# 20180616.net
KiCad netlist of a schematic drawn in Altium Designer
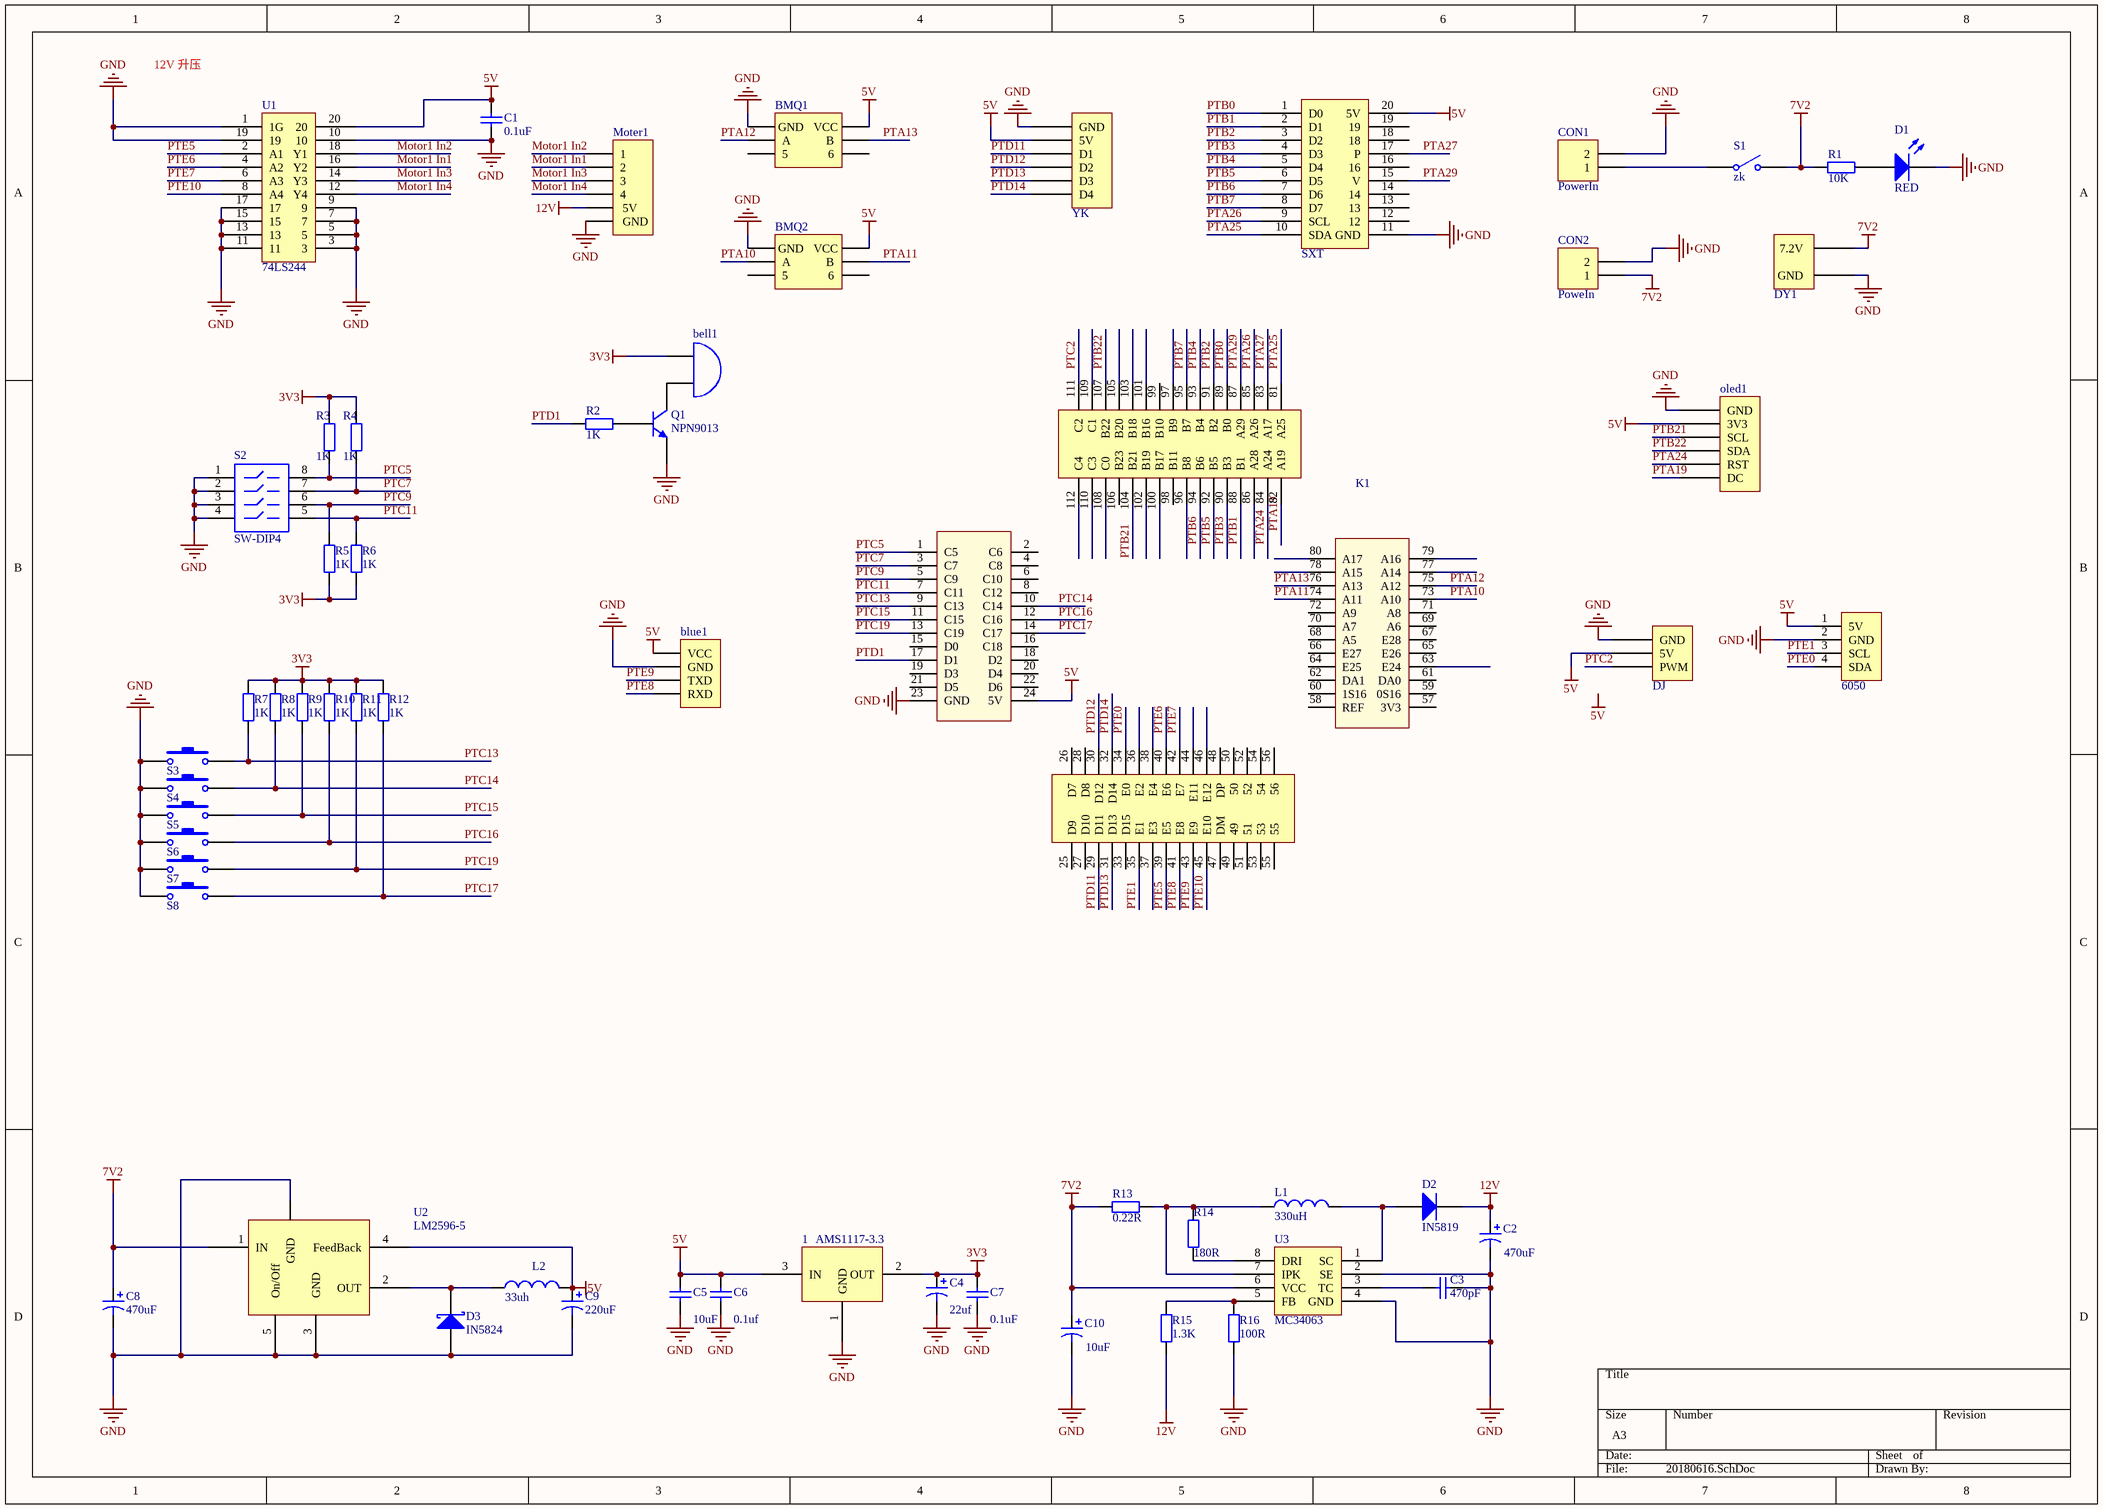
[diagram p0: 20180616.SchDoc]

(export (version "E")
  (design (tool "Eeschema 10.0.6"))
  (components
    (comp (ref "*") (value "6050") (footprint "HDR1X4") (libsource (lib "DS_zk") (part "6050")))
    (comp (ref "*1") (value "SXT") (footprint "SXT") (libsource (lib "DS_zk") (part "摄像头")))
    (comp (ref "*2") (value "YK") (footprint "HDR1X6") (libsource (lib "DS_zk") (part "遥控")))
    (comp (ref "*7") (value "DJ") (footprint "HDR1X3") (libsource (lib "DS_zk") (part "舵机")))
    (comp (ref "1")
      (value "AMS1117-3.3")
      (footprint "lm1117-5v")
      (libsource (lib "红牛板Schlib") (part "LT1117-3.3"))
    )
    (comp (ref "bell1")
      (value "Bell")
      (footprint "bezzer")
      (description "Electrical Bell")
      (fields (field (name "PUBLISHER") "Altium Limited"))
      (libsource (lib "Miscellaneous Devices") (part "Bell"))
    )
    (comp (ref "blue1") (value "blueteeth2") (footprint "HDR1X4") (libsource (lib "LY") (part "blueteeth")))
    (comp (ref "BMQ1") (value "encode_1") (footprint "HDR2X3") (libsource (lib "主控板原理图") (part "encode")))
    (comp (ref "BMQ2") (value "encode_2") (footprint "HDR2X3") (libsource (lib "主控板原理图") (part "encode")))
    (comp (ref "C1")
      (value "0.1uF")
      (footprint "0603")
      (description "Capacitor (Semiconductor SIM Model)")
      (fields (field (name "PUBLISHER") "Altium Limited"))
      (libsource (lib "Miscellaneous Devices") (part "Cap Semi"))
    )
    (comp (ref "C2")
      (value "470uF")
      (footprint "470UF")
      (description "Polarized Capacitor (Surface Mount)")
      (fields (field (name "PUBLISHER") "Altium Limited"))
      (libsource (lib "Miscellaneous Devices") (part "Cap Pol3"))
    )
    (comp (ref "C3")
      (value "470pF")
      (footprint "0805")
      (description "Capacitor (Semiconductor SIM Model)")
      (fields (field (name "PUBLISHER") "Altium Limited"))
      (libsource (lib "Miscellaneous Devices") (part "Cap Semi"))
    )
    (comp (ref "C4")
      (value "22uf")
      (footprint "0805")
      (description "Polarized Capacitor (Radial)")
      (fields (field (name "Comment") "Cap Pol1") (field (name "PUBLISHER") "Altium Limited"))
      (libsource (lib "Miscellaneous Devices") (part "Cap Pol1"))
    )
    (comp (ref "C5")
      (value "10uF")
      (footprint "0805")
      (description "Capacitor")
      (fields (field (name "Comment") "Cap") (field (name "PUBLISHER") "Altium Limited"))
      (libsource (lib "Miscellaneous Devices") (part "Cap"))
    )
    (comp (ref "C6")
      (value "0.1uf")
      (footprint "0805")
      (description "Capacitor")
      (fields (field (name "Comment") "Cap") (field (name "PUBLISHER") "Altium Limited"))
      (libsource (lib "Miscellaneous Devices") (part "Cap"))
    )
    (comp (ref "C7")
      (value "0.1uF")
      (footprint "0805")
      (description "Capacitor")
      (fields (field (name "Comment") "Cap") (field (name "PUBLISHER") "Altium Limited"))
      (libsource (lib "Miscellaneous Devices") (part "Cap"))
    )
    (comp (ref "C8")
      (value "470uF")
      (footprint "470uF")
      (description "Polarized Capacitor (Radial)")
      (fields (field (name "Comment") "Cap Pol1") (field (name "PUBLISHER") "Altium Limited"))
      (libsource (lib "主控板原理图") (part "Cap Pol1"))
    )
    (comp (ref "C9")
      (value "220uF")
      (footprint "220uf")
      (description "Polarized Capacitor (Radial)")
      (fields (field (name "Comment") "Cap Pol1") (field (name "PUBLISHER") "Altium Limited"))
      (libsource (lib "主控板原理图") (part "Cap Pol1"))
    )
    (comp (ref "C10")
      (value "10uF")
      (footprint "0805")
      (description "Polarized Capacitor (Surface Mount)")
      (fields (field (name "PUBLISHER") "Altium Limited"))
      (libsource (lib "Miscellaneous Devices") (part "Cap Pol3"))
    )
    (comp (ref "CON1")
      (value "PowerIn")
      (footprint "DIZUO")
      (description "Header, 2-Pin")
      (fields (field (name "PUBLISHER") "Altium Limited"))
      (libsource (lib "Miscellaneous Connectors") (part "Header 2"))
    )
    (comp (ref "CON2")
      (value "PoweIn")
      (footprint "KF301-2P")
      (description "Header, 2-Pin")
      (fields (field (name "PUBLISHER") "Altium Limited"))
      (libsource (lib "Miscellaneous Connectors") (part "Header 2"))
    )
    (comp (ref "D1")
      (value "RED")
      (footprint "0805LED")
      (description "Typical RED, GREEN, YELLOW, AMBER GaAs LED")
      (fields (field (name "PUBLISHER") "Altium Limited"))
      (libsource (lib "主控板原理图") (part "LED2"))
    )
    (comp (ref "D2")
      (value "IN5819")
      (footprint "1206(3216)")
      (description "Default Diode")
      (fields (field (name "PUBLISHER") "Altium Limited"))
      (libsource (lib "Miscellaneous Devices") (part "Diode"))
    )
    (comp (ref "D3") (value "IN5824") (footprint "1N5824") (libsource (lib "主控板原理图") (part "IN5824")))
    (comp (ref "DY1") (value "H1") (footprint "HDR1X2") (libsource (lib "DS_zk") (part "H1")))
    (comp (ref "K1") (value "K60") (footprint "K60") (libsource (lib "主控板原理图") (part "K60")))
    (comp (ref "L1")
      (value "330uH")
      (footprint "diangan")
      (description "Inductor")
      (fields (field (name "PUBLISHER") "Altium Limited"))
      (libsource (lib "Miscellaneous Devices") (part "Inductor"))
    )
    (comp (ref "L2")
      (value "33uh")
      (footprint "diangan")
      (description "Inductor")
      (fields (field (name "PUBLISHER") "Altium Limited"))
      (libsource (lib "主控板原理图") (part "Inductor"))
    )
    (comp (ref "Moter1") (value "Motor") (footprint "HDR1X6") (libsource (lib "主控板原理图") (part "Motor")))
    (comp (ref "oled1") (value "OLED") (footprint "HDR1X6") (libsource (lib "LY") (part "OLED")))
    (comp (ref "Q1")
      (value "NPN9013")
      (footprint "npn9013")
      (description "NPN General Purpose Amplifier")
      (fields (field (name "PUBLISHER") "Altium Limited"))
      (libsource (lib "Miscellaneous Devices") (part "2N3904"))
    )
    (comp (ref "R1")
      (value "10K")
      (footprint "0805")
      (description "Resistor")
      (fields (field (name "Comment") "Res2") (field (name "PUBLISHER") "Altium Limited"))
      (libsource (lib "") (part "Res2_2"))
    )
    (comp (ref "R2")
      (value "1K")
      (footprint "0805")
      (description "Resistor")
      (fields (field (name "Comment") "Res2") (field (name "PUBLISHER") "Altium Limited"))
      (libsource (lib "") (part "Res2_1"))
    )
    (comp (ref "R3")
      (value "1K")
      (footprint "0805")
      (description "Resistor")
      (fields (field (name "Comment") "Res2") (field (name "PUBLISHER") "Altium Limited"))
      (libsource (lib "") (part "Res2_3"))
    )
    (comp (ref "R4")
      (value "1K")
      (footprint "0805")
      (description "Resistor")
      (fields (field (name "Comment") "Res2") (field (name "PUBLISHER") "Altium Limited"))
      (libsource (lib "") (part "Res2_3"))
    )
    (comp (ref "R5")
      (value "1K")
      (footprint "0805")
      (description "Resistor")
      (fields (field (name "Comment") "Res2") (field (name "PUBLISHER") "Altium Limited"))
      (libsource (lib "主控板原理图") (part "Res2"))
    )
    (comp (ref "R6")
      (value "1K")
      (footprint "0805")
      (description "Resistor")
      (fields (field (name "Comment") "Res2") (field (name "PUBLISHER") "Altium Limited"))
      (libsource (lib "") (part "Res2_3"))
    )
    (comp (ref "R7")
      (value "1K")
      (footprint "0805")
      (description "Resistor")
      (fields (field (name "Comment") "Res2") (field (name "PUBLISHER") "Altium Limited"))
      (libsource (lib "") (part "Res2_3"))
    )
    (comp (ref "R8")
      (value "1K")
      (footprint "0805")
      (description "Resistor")
      (fields (field (name "Comment") "Res2") (field (name "PUBLISHER") "Altium Limited"))
      (libsource (lib "") (part "Res2_3"))
    )
    (comp (ref "R9")
      (value "1K")
      (footprint "0805")
      (description "Resistor")
      (fields (field (name "Comment") "Res2") (field (name "PUBLISHER") "Altium Limited"))
      (libsource (lib "") (part "Res2_3"))
    )
    (comp (ref "R10")
      (value "1K")
      (footprint "0805")
      (description "Resistor")
      (fields (field (name "Comment") "Res2") (field (name "PUBLISHER") "Altium Limited"))
      (libsource (lib "") (part "Res2_3"))
    )
    (comp (ref "R11")
      (value "1K")
      (footprint "0805")
      (description "Resistor")
      (fields (field (name "Comment") "Res2") (field (name "PUBLISHER") "Altium Limited"))
      (libsource (lib "") (part "Res2_3"))
    )
    (comp (ref "R12")
      (value "1K")
      (footprint "0805")
      (description "Resistor")
      (fields (field (name "Comment") "Res2") (field (name "PUBLISHER") "Altium Limited"))
      (libsource (lib "") (part "Res2_3"))
    )
    (comp (ref "R13")
      (value "0.22R")
      (footprint "0805")
      (description "Resistor")
      (fields (field (name "PUBLISHER") "Altium Limited"))
      (libsource (lib "") (part "Res2_2"))
    )
    (comp (ref "R14")
      (value "180R")
      (footprint "0805")
      (description "Resistor")
      (fields (field (name "PUBLISHER") "Altium Limited"))
      (libsource (lib "") (part "Res2_1"))
    )
    (comp (ref "R15")
      (value "1.3K")
      (footprint "0805")
      (description "Resistor")
      (fields (field (name "PUBLISHER") "Altium Limited"))
      (libsource (lib "Miscellaneous Devices") (part "Res2"))
    )
    (comp (ref "R16")
      (value "100R")
      (footprint "0805")
      (description "Resistor")
      (fields (field (name "PUBLISHER") "Altium Limited"))
      (libsource (lib "Miscellaneous Devices") (part "Res2"))
    )
    (comp (ref "S1")
      (value "zk")
      (footprint "SWITCH-MID")
      (description "Single-Pole, Single-Throw Switch")
      (fields (field (name "PUBLISHER") "Altium Limited"))
      (libsource (lib "Miscellaneous Devices") (part "SW-SPST"))
    )
    (comp (ref "S2")
      (value "SW-DIP4")
      (footprint "BMKG")
      (description "DIP Switch")
      (fields (field (name "PUBLISHER") "Altium Limited"))
      (libsource (lib "主控板原理图") (part "SW-DIP4"))
    )
    (comp (ref "S3")
      (value "SW-PB")
      (footprint "BUTTON")
      (description "Switch")
      (fields (field (name "PUBLISHER") "Altium Limited"))
      (libsource (lib "主控板原理图") (part "SW-PB"))
    )
    (comp (ref "S4")
      (value "SW-PB")
      (footprint "BUTTON")
      (description "Switch")
      (fields (field (name "PUBLISHER") "Altium Limited"))
      (libsource (lib "主控板原理图") (part "SW-PB"))
    )
    (comp (ref "S5")
      (value "SW-PB")
      (footprint "BUTTON")
      (description "Switch")
      (fields (field (name "PUBLISHER") "Altium Limited"))
      (libsource (lib "主控板原理图") (part "SW-PB"))
    )
    (comp (ref "S6")
      (value "SW-PB")
      (footprint "BUTTON")
      (description "Switch")
      (fields (field (name "PUBLISHER") "Altium Limited"))
      (libsource (lib "主控板原理图") (part "SW-PB"))
    )
    (comp (ref "S7")
      (value "SW-PB")
      (footprint "BUTTON")
      (description "Switch")
      (fields (field (name "PUBLISHER") "Altium Limited"))
      (libsource (lib "主控板原理图") (part "SW-PB"))
    )
    (comp (ref "S8")
      (value "SW-PB")
      (footprint "BUTTON")
      (description "Switch")
      (fields (field (name "PUBLISHER") "Altium Limited"))
      (libsource (lib "主控板原理图") (part "SW-PB"))
    )
    (comp (ref "U1") (value "74LS244") (footprint "74ls244DB") (libsource (lib "ly") (part "74LS244")))
    (comp (ref "U2") (value "LM2596-5") (footprint "LM2596") (libsource (lib "主控板原理图") (part "LM2596")))
    (comp (ref "U3") (value "MC34063") (footprint "MC34063") (libsource (lib "LY") (part "MC34063")))
  )
  (nets
    (net (code "1") (name "/Motor1 In1") (class "Default")
      (node (ref "Moter1") (pin "2") (pinfunction "2_2") (pintype "passive"))
      (node (ref "U1") (pin "16") (pinfunction "Y2_16") (pintype "passive"))
    )
    (net (code "2") (name "/Motor1 In2") (class "Default")
      (node (ref "Moter1") (pin "1") (pinfunction "1_1") (pintype "passive"))
      (node (ref "U1") (pin "18") (pinfunction "Y1_18") (pintype "passive"))
    )
    (net (code "3") (name "/Motor1 In3") (class "Default")
      (node (ref "Moter1") (pin "3") (pinfunction "3_3") (pintype "passive"))
      (node (ref "U1") (pin "14") (pinfunction "Y3_14") (pintype "passive"))
    )
    (net (code "4") (name "/Motor1 In4") (class "Default")
      (node (ref "Moter1") (pin "4") (pinfunction "4_4") (pintype "passive"))
      (node (ref "U1") (pin "12") (pinfunction "Y4_12") (pintype "passive"))
    )
    (net (code "5") (name "/PTA10") (class "Default")
      (node (ref "BMQ2") (pin "3") (pinfunction "A_3") (pintype "passive"))
      (node (ref "K1") (pin "73") (pinfunction "A10_73") (pintype "passive"))
    )
    (net (code "6") (name "/PTA11") (class "Default")
      (node (ref "BMQ2") (pin "4") (pinfunction "B_4") (pintype "passive"))
      (node (ref "K1") (pin "74") (pinfunction "A11_74") (pintype "passive"))
    )
    (net (code "7") (name "/PTA12") (class "Default")
      (node (ref "BMQ1") (pin "3") (pinfunction "A_3") (pintype "passive"))
      (node (ref "K1") (pin "75") (pinfunction "A12_75") (pintype "passive"))
    )
    (net (code "8") (name "/PTA13") (class "Default")
      (node (ref "BMQ1") (pin "4") (pinfunction "B_4") (pintype "passive"))
      (node (ref "K1") (pin "76") (pinfunction "A13_76") (pintype "passive"))
    )
    (net (code "9") (name "/PTA19") (class "Default")
      (node (ref "K1") (pin "82") (pinfunction "A19_82") (pintype "passive"))
      (node (ref "oled1") (pin "6") (pinfunction "DC_6") (pintype "passive"))
    )
    (net (code "10") (name "/PTA24") (class "Default")
      (node (ref "K1") (pin "84") (pinfunction "A24_84") (pintype "passive"))
      (node (ref "oled1") (pin "5") (pinfunction "RST_5") (pintype "passive"))
    )
    (net (code "11") (name "/PTA25") (class "Default")
      (node (ref "*1") (pin "10") (pinfunction "SDA_10") (pintype "passive"))
      (node (ref "K1") (pin "81") (pinfunction "A25_81") (pintype "passive"))
    )
    (net (code "12") (name "/PTA26") (class "Default")
      (node (ref "*1") (pin "9") (pinfunction "SCL_9") (pintype "passive"))
      (node (ref "K1") (pin "85") (pinfunction "A26_85") (pintype "passive"))
    )
    (net (code "13") (name "/PTA27") (class "Default")
      (node (ref "*1") (pin "17") (pinfunction "P_17") (pintype "passive"))
      (node (ref "K1") (pin "83") (pinfunction "A17_83") (pintype "passive"))
    )
    (net (code "14") (name "/PTA29") (class "Default")
      (node (ref "*1") (pin "15") (pinfunction "V_15") (pintype "passive"))
      (node (ref "K1") (pin "87") (pinfunction "A29_87") (pintype "passive"))
    )
    (net (code "15") (name "/PTB0") (class "Default")
      (node (ref "*1") (pin "1") (pinfunction "D0_1") (pintype "passive"))
      (node (ref "K1") (pin "89") (pinfunction "B0_89") (pintype "passive"))
    )
    (net (code "16") (name "/PTB1") (class "Default")
      (node (ref "*1") (pin "2") (pinfunction "D1_2") (pintype "passive"))
      (node (ref "K1") (pin "88") (pinfunction "B1_88") (pintype "passive"))
    )
    (net (code "17") (name "/PTB2") (class "Default")
      (node (ref "*1") (pin "3") (pinfunction "D2_3") (pintype "passive"))
      (node (ref "K1") (pin "91") (pinfunction "B2_91") (pintype "passive"))
    )
    (net (code "18") (name "/PTB3") (class "Default")
      (node (ref "*1") (pin "4") (pinfunction "D3_4") (pintype "passive"))
      (node (ref "K1") (pin "90") (pinfunction "B3_90") (pintype "passive"))
    )
    (net (code "19") (name "/PTB4") (class "Default")
      (node (ref "*1") (pin "5") (pinfunction "D4_5") (pintype "passive"))
      (node (ref "K1") (pin "93") (pinfunction "B4_93") (pintype "passive"))
    )
    (net (code "20") (name "/PTB5") (class "Default")
      (node (ref "*1") (pin "6") (pinfunction "D5_6") (pintype "passive"))
      (node (ref "K1") (pin "92") (pinfunction "B5_92") (pintype "passive"))
    )
    (net (code "21") (name "/PTB6") (class "Default")
      (node (ref "*1") (pin "7") (pinfunction "D6_7") (pintype "passive"))
      (node (ref "K1") (pin "94") (pinfunction "B6_94") (pintype "passive"))
    )
    (net (code "22") (name "/PTB7") (class "Default")
      (node (ref "*1") (pin "8") (pinfunction "D7_8") (pintype "passive"))
      (node (ref "K1") (pin "95") (pinfunction "B7_95") (pintype "passive"))
    )
    (net (code "23") (name "/PTB21") (class "Default")
      (node (ref "K1") (pin "104") (pinfunction "B21_104") (pintype "passive"))
      (node (ref "oled1") (pin "3") (pinfunction "SCL_3") (pintype "passive"))
    )
    (net (code "24") (name "/PTB22") (class "Default")
      (node (ref "K1") (pin "107") (pinfunction "B22_107") (pintype "passive"))
      (node (ref "oled1") (pin "4") (pinfunction "SDA_4") (pintype "passive"))
    )
    (net (code "25") (name "/PTC2") (class "Default")
      (node (ref "*7") (pin "3") (pinfunction "PWM_3") (pintype "passive"))
      (node (ref "K1") (pin "111") (pinfunction "C2_111") (pintype "passive"))
    )
    (net (code "26") (name "/PTC5") (class "Default")
      (node (ref "K1") (pin "1") (pinfunction "C5_1") (pintype "passive"))
      (node (ref "R3") (pin "1") (pinfunction "1_1") (pintype "passive"))
      (node (ref "S2") (pin "8") (pinfunction "8_8") (pintype "passive"))
    )
    (net (code "27") (name "/PTC7") (class "Default")
      (node (ref "K1") (pin "3") (pinfunction "C7_3") (pintype "passive"))
      (node (ref "R4") (pin "1") (pinfunction "1_1") (pintype "passive"))
      (node (ref "S2") (pin "7") (pinfunction "7_7") (pintype "passive"))
    )
    (net (code "28") (name "/PTC9") (class "Default")
      (node (ref "K1") (pin "5") (pinfunction "C9_5") (pintype "passive"))
      (node (ref "R5") (pin "1") (pinfunction "1_1") (pintype "passive"))
      (node (ref "S2") (pin "6") (pinfunction "6_6") (pintype "passive"))
    )
    (net (code "29") (name "/PTC11") (class "Default")
      (node (ref "K1") (pin "7") (pinfunction "C11_7") (pintype "passive"))
      (node (ref "R6") (pin "2") (pinfunction "2_2") (pintype "passive"))
      (node (ref "S2") (pin "5") (pinfunction "5_5") (pintype "passive"))
    )
    (net (code "30") (name "/PTC13") (class "Default")
      (node (ref "K1") (pin "9") (pinfunction "C13_9") (pintype "passive"))
      (node (ref "R7") (pin "1") (pinfunction "1_1") (pintype "passive"))
      (node (ref "S3") (pin "2") (pinfunction "2_2") (pintype "passive"))
    )
    (net (code "31") (name "/PTC14") (class "Default")
      (node (ref "K1") (pin "10") (pinfunction "C14_10") (pintype "passive"))
      (node (ref "R8") (pin "1") (pinfunction "1_1") (pintype "passive"))
      (node (ref "S4") (pin "2") (pinfunction "2_2") (pintype "passive"))
    )
    (net (code "32") (name "/PTC15") (class "Default")
      (node (ref "K1") (pin "11") (pinfunction "C15_11") (pintype "passive"))
      (node (ref "R9") (pin "1") (pinfunction "1_1") (pintype "passive"))
      (node (ref "S5") (pin "2") (pinfunction "2_2") (pintype "passive"))
    )
    (net (code "33") (name "/PTC16") (class "Default")
      (node (ref "K1") (pin "12") (pinfunction "C16_12") (pintype "passive"))
      (node (ref "R10") (pin "1") (pinfunction "1_1") (pintype "passive"))
      (node (ref "S6") (pin "2") (pinfunction "2_2") (pintype "passive"))
    )
    (net (code "34") (name "/PTC17") (class "Default")
      (node (ref "K1") (pin "14") (pinfunction "C17_14") (pintype "passive"))
      (node (ref "R12") (pin "1") (pinfunction "1_1") (pintype "passive"))
      (node (ref "S8") (pin "2") (pinfunction "2_2") (pintype "passive"))
    )
    (net (code "35") (name "/PTC19") (class "Default")
      (node (ref "K1") (pin "13") (pinfunction "C19_13") (pintype "passive"))
      (node (ref "R11") (pin "1") (pinfunction "1_1") (pintype "passive"))
      (node (ref "S7") (pin "2") (pinfunction "2_2") (pintype "passive"))
    )
    (net (code "36") (name "/PTD1") (class "Default")
      (node (ref "K1") (pin "17") (pinfunction "D1_17") (pintype "passive"))
      (node (ref "R2") (pin "1") (pinfunction "1_1") (pintype "passive"))
    )
    (net (code "37") (name "/PTD11") (class "Default")
      (node (ref "*2") (pin "3") (pinfunction "D1_3") (pintype "passive"))
      (node (ref "K1") (pin "29") (pinfunction "D11_29") (pintype "passive"))
    )
    (net (code "38") (name "/PTD12") (class "Default")
      (node (ref "*2") (pin "4") (pinfunction "D2_4") (pintype "passive"))
      (node (ref "K1") (pin "30") (pinfunction "D12_30") (pintype "passive"))
    )
    (net (code "39") (name "/PTD13") (class "Default")
      (node (ref "*2") (pin "5") (pinfunction "D3_5") (pintype "passive"))
      (node (ref "K1") (pin "31") (pinfunction "D13_31") (pintype "passive"))
    )
    (net (code "40") (name "/PTD14") (class "Default")
      (node (ref "*2") (pin "6") (pinfunction "D4_6") (pintype "passive"))
      (node (ref "K1") (pin "32") (pinfunction "D14_32") (pintype "passive"))
    )
    (net (code "41") (name "/PTE0") (class "Default")
      (node (ref "*") (pin "4") (pinfunction "SDA_4") (pintype "passive"))
      (node (ref "K1") (pin "34") (pinfunction "E0_34") (pintype "passive"))
    )
    (net (code "42") (name "/PTE1") (class "Default")
      (node (ref "*") (pin "3") (pinfunction "SCL_3") (pintype "passive"))
      (node (ref "K1") (pin "35") (pinfunction "E1_35") (pintype "passive"))
    )
    (net (code "43") (name "/PTE5") (class "Default")
      (node (ref "K1") (pin "39") (pinfunction "E5_39") (pintype "passive"))
      (node (ref "U1") (pin "2") (pinfunction "A1_2") (pintype "passive"))
    )
    (net (code "44") (name "/PTE6") (class "Default")
      (node (ref "K1") (pin "40") (pinfunction "E6_40") (pintype "passive"))
      (node (ref "U1") (pin "4") (pinfunction "A2_4") (pintype "passive"))
    )
    (net (code "45") (name "/PTE7") (class "Default")
      (node (ref "K1") (pin "42") (pinfunction "E7_42") (pintype "passive"))
      (node (ref "U1") (pin "6") (pinfunction "A3_6") (pintype "passive"))
    )
    (net (code "46") (name "/PTE8") (class "Default")
      (node (ref "K1") (pin "41") (pinfunction "E8_41") (pintype "passive"))
      (node (ref "blue1") (pin "4") (pinfunction "RXD_4") (pintype "passive"))
    )
    (net (code "47") (name "/PTE9") (class "Default")
      (node (ref "K1") (pin "43") (pinfunction "E9_43") (pintype "passive"))
      (node (ref "blue1") (pin "3") (pinfunction "TXD_3") (pintype "passive"))
    )
    (net (code "48") (name "/PTE10") (class "Default")
      (node (ref "K1") (pin "45") (pinfunction "E10_45") (pintype "passive"))
      (node (ref "U1") (pin "8") (pinfunction "A4_8") (pintype "passive"))
    )
    (net (code "49") (name "3V3") (class "Default")
      (node (ref "1") (pin "2") (pinfunction "OUT_2") (pintype "open_emitter"))
      (node (ref "C4") (pin "1") (pinfunction "1_1") (pintype "passive"))
      (node (ref "C7") (pin "2") (pinfunction "2_2") (pintype "passive"))
      (node (ref "R10") (pin "2") (pinfunction "2_2") (pintype "passive"))
      (node (ref "R11") (pin "2") (pinfunction "2_2") (pintype "passive"))
      (node (ref "R12") (pin "2") (pinfunction "2_2") (pintype "passive"))
      (node (ref "R3") (pin "2") (pinfunction "2_2") (pintype "passive"))
      (node (ref "R4") (pin "2") (pinfunction "2_2") (pintype "passive"))
      (node (ref "R5") (pin "2") (pinfunction "2_2") (pintype "passive"))
      (node (ref "R6") (pin "1") (pinfunction "1_1") (pintype "passive"))
      (node (ref "R7") (pin "2") (pinfunction "2_2") (pintype "passive"))
      (node (ref "R8") (pin "2") (pinfunction "2_2") (pintype "passive"))
      (node (ref "R9") (pin "2") (pinfunction "2_2") (pintype "passive"))
      (node (ref "bell1") (pin "1") (pinfunction "A_1") (pintype "passive"))
    )
    (net (code "50") (name "5V") (class "Default")
      (node (ref "*") (pin "1") (pinfunction "5V_1") (pintype "passive"))
      (node (ref "*1") (pin "20") (pinfunction "5V_20") (pintype "passive"))
      (node (ref "*2") (pin "2") (pinfunction "5V_2") (pintype "passive"))
      (node (ref "*7") (pin "2") (pinfunction "5V_2") (pintype "passive"))
      (node (ref "1") (pin "3") (pinfunction "IN_3") (pintype "open_emitter"))
      (node (ref "BMQ1") (pin "2") (pinfunction "VCC_2") (pintype "passive"))
      (node (ref "BMQ2") (pin "2") (pinfunction "VCC_2") (pintype "passive"))
      (node (ref "C1") (pin "2") (pinfunction "2_2") (pintype "passive"))
      (node (ref "C5") (pin "2") (pinfunction "2_2") (pintype "passive"))
      (node (ref "C6") (pin "2") (pinfunction "2_2") (pintype "passive"))
      (node (ref "C9") (pin "1") (pinfunction "1_1") (pintype "passive"))
      (node (ref "K1") (pin "24") (pinfunction "5V_24") (pintype "passive"))
      (node (ref "L2") (pin "2") (pinfunction "2_2") (pintype "passive"))
      (node (ref "U1") (pin "20") (pinfunction "20_20") (pintype "passive"))
      (node (ref "U2") (pin "4") (pinfunction "FeedBack_4") (pintype "passive"))
      (node (ref "blue1") (pin "1") (pinfunction "VCC_1") (pintype "passive"))
      (node (ref "oled1") (pin "2") (pinfunction "3V3_2") (pintype "passive"))
    )
    (net (code "51") (name "7V2") (class "Default")
      (node (ref "C10") (pin "1") (pinfunction "1_1") (pintype "passive"))
      (node (ref "C8") (pin "1") (pinfunction "1_1") (pintype "passive"))
      (node (ref "CON2") (pin "1") (pinfunction "1_1") (pintype "passive"))
      (node (ref "DY1") (pin "2") (pinfunction "7.2V_2") (pintype "passive"))
      (node (ref "R1") (pin "2") (pinfunction "2_2") (pintype "passive"))
      (node (ref "R13") (pin "2") (pinfunction "2_2") (pintype "passive"))
      (node (ref "S1") (pin "2") (pinfunction "NO_2") (pintype "passive"))
      (node (ref "U2") (pin "1") (pinfunction "IN_1") (pintype "passive"))
      (node (ref "U3") (pin "6") (pinfunction "VCC_6") (pintype "passive"))
    )
    (net (code "52") (name "12V") (class "Default")
      (node (ref "C2") (pin "1") (pinfunction "1_1") (pintype "passive"))
      (node (ref "D2") (pin "2") (pinfunction "K_2") (pintype "passive"))
      (node (ref "Moter1") (pin "5") (pinfunction "5V_5") (pintype "passive"))
      (node (ref "R15") (pin "2") (pinfunction "2_2") (pintype "passive"))
    )
    (net (code "53") (name "GND") (class "Default")
      (node (ref "*") (pin "2") (pinfunction "GND_2") (pintype "passive"))
      (node (ref "*1") (pin "11") (pinfunction "GND_11") (pintype "passive"))
      (node (ref "*2") (pin "1") (pinfunction "GND_1") (pintype "passive"))
      (node (ref "*7") (pin "1") (pinfunction "GND_1") (pintype "passive"))
      (node (ref "1") (pin "1") (pinfunction "GND_1") (pintype "open_emitter"))
      (node (ref "BMQ1") (pin "1") (pinfunction "GND_1") (pintype "passive"))
      (node (ref "BMQ2") (pin "1") (pinfunction "GND_1") (pintype "passive"))
      (node (ref "C1") (pin "1") (pinfunction "1_1") (pintype "passive"))
      (node (ref "C10") (pin "2") (pinfunction "2_2") (pintype "passive"))
      (node (ref "C2") (pin "2") (pinfunction "2_2") (pintype "passive"))
      (node (ref "C3") (pin "2") (pinfunction "2_2") (pintype "passive"))
      (node (ref "C4") (pin "2") (pinfunction "2_2") (pintype "passive"))
      (node (ref "C5") (pin "1") (pinfunction "1_1") (pintype "passive"))
      (node (ref "C6") (pin "1") (pinfunction "1_1") (pintype "passive"))
      (node (ref "C7") (pin "1") (pinfunction "1_1") (pintype "passive"))
      (node (ref "C8") (pin "2") (pinfunction "2_2") (pintype "passive"))
      (node (ref "C9") (pin "2") (pinfunction "2_2") (pintype "passive"))
      (node (ref "CON1") (pin "2") (pinfunction "2_2") (pintype "passive"))
      (node (ref "CON2") (pin "2") (pinfunction "2_2") (pintype "passive"))
      (node (ref "D1") (pin "2") (pinfunction "K_2") (pintype "passive"))
      (node (ref "D3") (pin "2") (pinfunction "K_2") (pintype "passive"))
      (node (ref "DY1") (pin "1") (pinfunction "GND_1") (pintype "passive"))
      (node (ref "K1") (pin "23") (pinfunction "GND_23") (pintype "passive"))
      (node (ref "Moter1") (pin "6") (pinfunction "GND_6") (pintype "passive"))
      (node (ref "Q1") (pin "1") (pinfunction "E_1") (pintype "passive"))
      (node (ref "R16") (pin "2") (pinfunction "2_2") (pintype "passive"))
      (node (ref "S2") (pin "1") (pinfunction "1_1") (pintype "passive"))
      (node (ref "S2") (pin "2") (pinfunction "2_2") (pintype "passive"))
      (node (ref "S2") (pin "3") (pinfunction "3_3") (pintype "passive"))
      (node (ref "S2") (pin "4") (pinfunction "4_4") (pintype "passive"))
      (node (ref "S3") (pin "1") (pinfunction "1_1") (pintype "passive"))
      (node (ref "S4") (pin "1") (pinfunction "1_1") (pintype "passive"))
      (node (ref "S5") (pin "1") (pinfunction "1_1") (pintype "passive"))
      (node (ref "S6") (pin "1") (pinfunction "1_1") (pintype "passive"))
      (node (ref "S7") (pin "1") (pinfunction "1_1") (pintype "passive"))
      (node (ref "S8") (pin "1") (pinfunction "1_1") (pintype "passive"))
      (node (ref "U1") (pin "1") (pinfunction "1G_1") (pintype "passive"))
      (node (ref "U1") (pin "10") (pinfunction "10_10") (pintype "passive"))
      (node (ref "U1") (pin "11") (pinfunction "11_11") (pintype "passive"))
      (node (ref "U1") (pin "13") (pinfunction "13_13") (pintype "passive"))
      (node (ref "U1") (pin "15") (pinfunction "15_15") (pintype "passive"))
      (node (ref "U1") (pin "17") (pinfunction "17_17") (pintype "passive"))
      (node (ref "U1") (pin "19") (pinfunction "19_19") (pintype "passive"))
      (node (ref "U1") (pin "3") (pinfunction "3_3") (pintype "passive"))
      (node (ref "U1") (pin "5") (pinfunction "5_5") (pintype "passive"))
      (node (ref "U1") (pin "7") (pinfunction "7_7") (pintype "passive"))
      (node (ref "U1") (pin "9") (pinfunction "9_9") (pintype "passive"))
      (node (ref "U2") (pin "3") (pinfunction "GND_3") (pintype "passive"))
      (node (ref "U2") (pin "5") (pinfunction "On/Off_5") (pintype "passive"))
      (node (ref "U2") (pin "6") (pinfunction "GND_6") (pintype "passive"))
      (node (ref "U3") (pin "2") (pinfunction "SE_2") (pintype "passive"))
      (node (ref "U3") (pin "4") (pinfunction "GND_4") (pintype "passive"))
      (node (ref "blue1") (pin "2") (pinfunction "GND_2") (pintype "passive"))
      (node (ref "oled1") (pin "1") (pinfunction "GND_1") (pintype "passive"))
    )
    (net (code "54") (name "Net-(D1-A)") (class "Default")
      (node (ref "D1") (pin "1") (pinfunction "A_1") (pintype "passive"))
      (node (ref "R1") (pin "1") (pinfunction "1_1") (pintype "passive"))
    )
    (net (code "55") (name "Net-(D2-A)") (class "Default")
      (node (ref "D2") (pin "1") (pinfunction "A_1") (pintype "passive"))
      (node (ref "L1") (pin "2") (pinfunction "2_2") (pintype "passive"))
      (node (ref "U3") (pin "1") (pinfunction "SC_1") (pintype "passive"))
    )
    (net (code "56") (name "Net-(D3-A)") (class "Default")
      (node (ref "D3") (pin "1") (pinfunction "A_1") (pintype "passive"))
      (node (ref "L2") (pin "1") (pinfunction "1_1") (pintype "passive"))
      (node (ref "U2") (pin "2") (pinfunction "OUT_2") (pintype "passive"))
    )
    (net (code "57") (name "Net-(Q1-B)") (class "Default")
      (node (ref "Q1") (pin "2") (pinfunction "B_2") (pintype "passive"))
      (node (ref "R2") (pin "2") (pinfunction "2_2") (pintype "passive"))
    )
    (net (code "58") (name "Net-(Q1-C)") (class "Default")
      (node (ref "Q1") (pin "3") (pinfunction "C_3") (pintype "passive"))
      (node (ref "bell1") (pin "2") (pinfunction "B_2") (pintype "passive"))
    )
    (net (code "59") (name "Net-(S1-COMMON)") (class "Default")
      (node (ref "CON1") (pin "1") (pinfunction "1_1") (pintype "passive"))
      (node (ref "S1") (pin "1") (pinfunction "COMMON_1") (pintype "passive"))
    )
    (net (code "60") (name "Net-(U3-DRI)") (class "Default")
      (node (ref "R14") (pin "1") (pinfunction "1_1") (pintype "passive"))
      (node (ref "U3") (pin "8") (pinfunction "DRI_8") (pintype "passive"))
    )
    (net (code "61") (name "Net-(U3-FB)") (class "Default")
      (node (ref "R15") (pin "1") (pinfunction "1_1") (pintype "passive"))
      (node (ref "R16") (pin "1") (pinfunction "1_1") (pintype "passive"))
      (node (ref "U3") (pin "5") (pinfunction "FB_5") (pintype "passive"))
    )
    (net (code "62") (name "Net-(U3-IPK)") (class "Default")
      (node (ref "L1") (pin "1") (pinfunction "1_1") (pintype "passive"))
      (node (ref "R13") (pin "1") (pinfunction "1_1") (pintype "passive"))
      (node (ref "R14") (pin "2") (pinfunction "2_2") (pintype "passive"))
      (node (ref "U3") (pin "7") (pinfunction "IPK_7") (pintype "passive"))
    )
    (net (code "63") (name "Net-(U3-TC)") (class "Default")
      (node (ref "C3") (pin "1") (pinfunction "1_1") (pintype "passive"))
      (node (ref "U3") (pin "3") (pinfunction "TC_3") (pintype "passive"))
    )
    (net (code "64") (name "unconnected-(*1-Pad12)") (class "Default")
      (node (ref "*1") (pin "12") (pinfunction "12_12") (pintype "passive"))
    )
    (net (code "65") (name "unconnected-(*1-Pad13)") (class "Default")
      (node (ref "*1") (pin "13") (pinfunction "13_13") (pintype "passive"))
    )
    (net (code "66") (name "unconnected-(*1-Pad14)") (class "Default")
      (node (ref "*1") (pin "14") (pinfunction "14_14") (pintype "passive"))
    )
    (net (code "67") (name "unconnected-(*1-Pad16)") (class "Default")
      (node (ref "*1") (pin "16") (pinfunction "16_16") (pintype "passive"))
    )
    (net (code "68") (name "unconnected-(*1-Pad18)") (class "Default")
      (node (ref "*1") (pin "18") (pinfunction "18_18") (pintype "passive"))
    )
    (net (code "69") (name "unconnected-(*1-Pad19)") (class "Default")
      (node (ref "*1") (pin "19") (pinfunction "19_19") (pintype "passive"))
    )
    (net (code "70") (name "unconnected-(BMQ1-Pad5)") (class "Default")
      (node (ref "BMQ1") (pin "5") (pinfunction "5_5") (pintype "passive"))
    )
    (net (code "71") (name "unconnected-(BMQ1-Pad6)") (class "Default")
      (node (ref "BMQ1") (pin "6") (pinfunction "6_6") (pintype "passive"))
    )
    (net (code "72") (name "unconnected-(BMQ2-Pad5)") (class "Default")
      (node (ref "BMQ2") (pin "5") (pinfunction "5_5") (pintype "passive"))
    )
    (net (code "73") (name "unconnected-(BMQ2-Pad6)") (class "Default")
      (node (ref "BMQ2") (pin "6") (pinfunction "6_6") (pintype "passive"))
    )
    (net (code "74") (name "unconnected-(K1-0S16-Pad59)") (class "Default")
      (node (ref "K1") (pin "59") (pinfunction "0S16_59") (pintype "passive"))
    )
    (net (code "75") (name "unconnected-(K1-1S16-Pad60)") (class "Default")
      (node (ref "K1") (pin "60") (pinfunction "1S16_60") (pintype "passive"))
    )
    (net (code "76") (name "unconnected-(K1-3V3-Pad57)") (class "Default")
      (node (ref "K1") (pin "57") (pinfunction "3V3_57") (pintype "passive"))
    )
    (net (code "77") (name "unconnected-(K1-A5-Pad68)") (class "Default")
      (node (ref "K1") (pin "68") (pinfunction "A5_68") (pintype "passive"))
    )
    (net (code "78") (name "unconnected-(K1-A6-Pad69)") (class "Default")
      (node (ref "K1") (pin "69") (pinfunction "A6_69") (pintype "passive"))
    )
    (net (code "79") (name "unconnected-(K1-A7-Pad70)") (class "Default")
      (node (ref "K1") (pin "70") (pinfunction "A7_70") (pintype "passive"))
    )
    (net (code "80") (name "unconnected-(K1-A8-Pad71)") (class "Default")
      (node (ref "K1") (pin "71") (pinfunction "A8_71") (pintype "passive"))
    )
    (net (code "81") (name "unconnected-(K1-A9-Pad72)") (class "Default")
      (node (ref "K1") (pin "72") (pinfunction "A9_72") (pintype "passive"))
    )
    (net (code "82") (name "unconnected-(K1-A14-Pad77)") (class "Default")
      (node (ref "K1") (pin "77") (pinfunction "A14_77") (pintype "passive"))
    )
    (net (code "83") (name "unconnected-(K1-A15-Pad78)") (class "Default")
      (node (ref "K1") (pin "78") (pinfunction "A15_78") (pintype "passive"))
    )
    (net (code "84") (name "unconnected-(K1-A16-Pad79)") (class "Default")
      (node (ref "K1") (pin "79") (pinfunction "A16_79") (pintype "passive"))
    )
    (net (code "85") (name "unconnected-(K1-A17-Pad80)") (class "Default")
      (node (ref "K1") (pin "80") (pinfunction "A17_80") (pintype "passive"))
    )
    (net (code "86") (name "unconnected-(K1-A28-Pad86)") (class "Default")
      (node (ref "K1") (pin "86") (pinfunction "A28_86") (pintype "passive"))
    )
    (net (code "87") (name "unconnected-(K1-B8-Pad96)") (class "Default")
      (node (ref "K1") (pin "96") (pinfunction "B8_96") (pintype "passive"))
    )
    (net (code "88") (name "unconnected-(K1-B9-Pad97)") (class "Default")
      (node (ref "K1") (pin "97") (pinfunction "B9_97") (pintype "passive"))
    )
    (net (code "89") (name "unconnected-(K1-B10-Pad99)") (class "Default")
      (node (ref "K1") (pin "99") (pinfunction "B10_99") (pintype "passive"))
    )
    (net (code "90") (name "unconnected-(K1-B11-Pad98)") (class "Default")
      (node (ref "K1") (pin "98") (pinfunction "B11_98") (pintype "passive"))
    )
    (net (code "91") (name "unconnected-(K1-B16-Pad101)") (class "Default")
      (node (ref "K1") (pin "101") (pinfunction "B16_101") (pintype "passive"))
    )
    (net (code "92") (name "unconnected-(K1-B17-Pad100)") (class "Default")
      (node (ref "K1") (pin "100") (pinfunction "B17_100") (pintype "passive"))
    )
    (net (code "93") (name "unconnected-(K1-B18-Pad103)") (class "Default")
      (node (ref "K1") (pin "103") (pinfunction "B18_103") (pintype "passive"))
    )
    (net (code "94") (name "unconnected-(K1-B19-Pad102)") (class "Default")
      (node (ref "K1") (pin "102") (pinfunction "B19_102") (pintype "passive"))
    )
    (net (code "95") (name "unconnected-(K1-B20-Pad105)") (class "Default")
      (node (ref "K1") (pin "105") (pinfunction "B20_105") (pintype "passive"))
    )
    (net (code "96") (name "unconnected-(K1-B23-Pad106)") (class "Default")
      (node (ref "K1") (pin "106") (pinfunction "B23_106") (pintype "passive"))
    )
    (net (code "97") (name "unconnected-(K1-C0-Pad108)") (class "Default")
      (node (ref "K1") (pin "108") (pinfunction "C0_108") (pintype "passive"))
    )
    (net (code "98") (name "unconnected-(K1-C1-Pad109)") (class "Default")
      (node (ref "K1") (pin "109") (pinfunction "C1_109") (pintype "passive"))
    )
    (net (code "99") (name "unconnected-(K1-C3-Pad110)") (class "Default")
      (node (ref "K1") (pin "110") (pinfunction "C3_110") (pintype "passive"))
    )
    (net (code "100") (name "unconnected-(K1-C4-Pad112)") (class "Default")
      (node (ref "K1") (pin "112") (pinfunction "C4_112") (pintype "passive"))
    )
    (net (code "101") (name "unconnected-(K1-C6-Pad2)") (class "Default")
      (node (ref "K1") (pin "2") (pinfunction "C6_2") (pintype "passive"))
    )
    (net (code "102") (name "unconnected-(K1-C8-Pad4)") (class "Default")
      (node (ref "K1") (pin "4") (pinfunction "C8_4") (pintype "passive"))
    )
    (net (code "103") (name "unconnected-(K1-C10-Pad6)") (class "Default")
      (node (ref "K1") (pin "6") (pinfunction "C10_6") (pintype "passive"))
    )
    (net (code "104") (name "unconnected-(K1-C12-Pad8)") (class "Default")
      (node (ref "K1") (pin "8") (pinfunction "C12_8") (pintype "passive"))
    )
    (net (code "105") (name "unconnected-(K1-C18-Pad16)") (class "Default")
      (node (ref "K1") (pin "16") (pinfunction "C18_16") (pintype "passive"))
    )
    (net (code "106") (name "unconnected-(K1-D0-Pad15)") (class "Default")
      (node (ref "K1") (pin "15") (pinfunction "D0_15") (pintype "passive"))
    )
    (net (code "107") (name "unconnected-(K1-D2-Pad18)") (class "Default")
      (node (ref "K1") (pin "18") (pinfunction "D2_18") (pintype "passive"))
    )
    (net (code "108") (name "unconnected-(K1-D3-Pad19)") (class "Default")
      (node (ref "K1") (pin "19") (pinfunction "D3_19") (pintype "passive"))
    )
    (net (code "109") (name "unconnected-(K1-D4-Pad20)") (class "Default")
      (node (ref "K1") (pin "20") (pinfunction "D4_20") (pintype "passive"))
    )
    (net (code "110") (name "unconnected-(K1-D5-Pad21)") (class "Default")
      (node (ref "K1") (pin "21") (pinfunction "D5_21") (pintype "passive"))
    )
    (net (code "111") (name "unconnected-(K1-D6-Pad22)") (class "Default")
      (node (ref "K1") (pin "22") (pinfunction "D6_22") (pintype "passive"))
    )
    (net (code "112") (name "unconnected-(K1-D7-Pad26)") (class "Default")
      (node (ref "K1") (pin "26") (pinfunction "D7_26") (pintype "passive"))
    )
    (net (code "113") (name "unconnected-(K1-D8-Pad28)") (class "Default")
      (node (ref "K1") (pin "28") (pinfunction "D8_28") (pintype "passive"))
    )
    (net (code "114") (name "unconnected-(K1-D9-Pad25)") (class "Default")
      (node (ref "K1") (pin "25") (pinfunction "D9_25") (pintype "passive"))
    )
    (net (code "115") (name "unconnected-(K1-D10-Pad27)") (class "Default")
      (node (ref "K1") (pin "27") (pinfunction "D10_27") (pintype "passive"))
    )
    (net (code "116") (name "unconnected-(K1-D15-Pad33)") (class "Default")
      (node (ref "K1") (pin "33") (pinfunction "D15_33") (pintype "passive"))
    )
    (net (code "117") (name "unconnected-(K1-DA0-Pad61)") (class "Default")
      (node (ref "K1") (pin "61") (pinfunction "DA0_61") (pintype "passive"))
    )
    (net (code "118") (name "unconnected-(K1-DA1-Pad62)") (class "Default")
      (node (ref "K1") (pin "62") (pinfunction "DA1_62") (pintype "passive"))
    )
    (net (code "119") (name "unconnected-(K1-DM-Pad47)") (class "Default")
      (node (ref "K1") (pin "47") (pinfunction "DM_47") (pintype "passive"))
    )
    (net (code "120") (name "unconnected-(K1-DP-Pad48)") (class "Default")
      (node (ref "K1") (pin "48") (pinfunction "DP_48") (pintype "passive"))
    )
    (net (code "121") (name "unconnected-(K1-E2-Pad36)") (class "Default")
      (node (ref "K1") (pin "36") (pinfunction "E2_36") (pintype "passive"))
    )
    (net (code "122") (name "unconnected-(K1-E3-Pad37)") (class "Default")
      (node (ref "K1") (pin "37") (pinfunction "E3_37") (pintype "passive"))
    )
    (net (code "123") (name "unconnected-(K1-E4-Pad38)") (class "Default")
      (node (ref "K1") (pin "38") (pinfunction "E4_38") (pintype "passive"))
    )
    (net (code "124") (name "unconnected-(K1-E11-Pad44)") (class "Default")
      (node (ref "K1") (pin "44") (pinfunction "E11_44") (pintype "passive"))
    )
    (net (code "125") (name "unconnected-(K1-E12-Pad46)") (class "Default")
      (node (ref "K1") (pin "46") (pinfunction "E12_46") (pintype "passive"))
    )
    (net (code "126") (name "unconnected-(K1-E24-Pad63)") (class "Default")
      (node (ref "K1") (pin "63") (pinfunction "E24_63") (pintype "passive"))
    )
    (net (code "127") (name "unconnected-(K1-E25-Pad64)") (class "Default")
      (node (ref "K1") (pin "64") (pinfunction "E25_64") (pintype "passive"))
    )
    (net (code "128") (name "unconnected-(K1-E26-Pad65)") (class "Default")
      (node (ref "K1") (pin "65") (pinfunction "E26_65") (pintype "passive"))
    )
    (net (code "129") (name "unconnected-(K1-E27-Pad66)") (class "Default")
      (node (ref "K1") (pin "66") (pinfunction "E27_66") (pintype "passive"))
    )
    (net (code "130") (name "unconnected-(K1-E28-Pad67)") (class "Default")
      (node (ref "K1") (pin "67") (pinfunction "E28_67") (pintype "passive"))
    )
    (net (code "131") (name "unconnected-(K1-Pad49)") (class "Default")
      (node (ref "K1") (pin "49") (pinfunction "49_49") (pintype "passive"))
    )
    (net (code "132") (name "unconnected-(K1-Pad50)") (class "Default")
      (node (ref "K1") (pin "50") (pinfunction "50_50") (pintype "passive"))
    )
    (net (code "133") (name "unconnected-(K1-Pad51)") (class "Default")
      (node (ref "K1") (pin "51") (pinfunction "51_51") (pintype "passive"))
    )
    (net (code "134") (name "unconnected-(K1-Pad52)") (class "Default")
      (node (ref "K1") (pin "52") (pinfunction "52_52") (pintype "passive"))
    )
    (net (code "135") (name "unconnected-(K1-Pad53)") (class "Default")
      (node (ref "K1") (pin "53") (pinfunction "53_53") (pintype "passive"))
    )
    (net (code "136") (name "unconnected-(K1-Pad54)") (class "Default")
      (node (ref "K1") (pin "54") (pinfunction "54_54") (pintype "passive"))
    )
    (net (code "137") (name "unconnected-(K1-Pad55)") (class "Default")
      (node (ref "K1") (pin "55") (pinfunction "55_55") (pintype "passive"))
    )
    (net (code "138") (name "unconnected-(K1-Pad56)") (class "Default")
      (node (ref "K1") (pin "56") (pinfunction "56_56") (pintype "passive"))
    )
    (net (code "139") (name "unconnected-(K1-REF-Pad58)") (class "Default")
      (node (ref "K1") (pin "58") (pinfunction "REF_58") (pintype "passive"))
    )
  )
)
